# Escorna_CPU_2_10.net
KiCad netlist of a schematic drawn in EAGLE
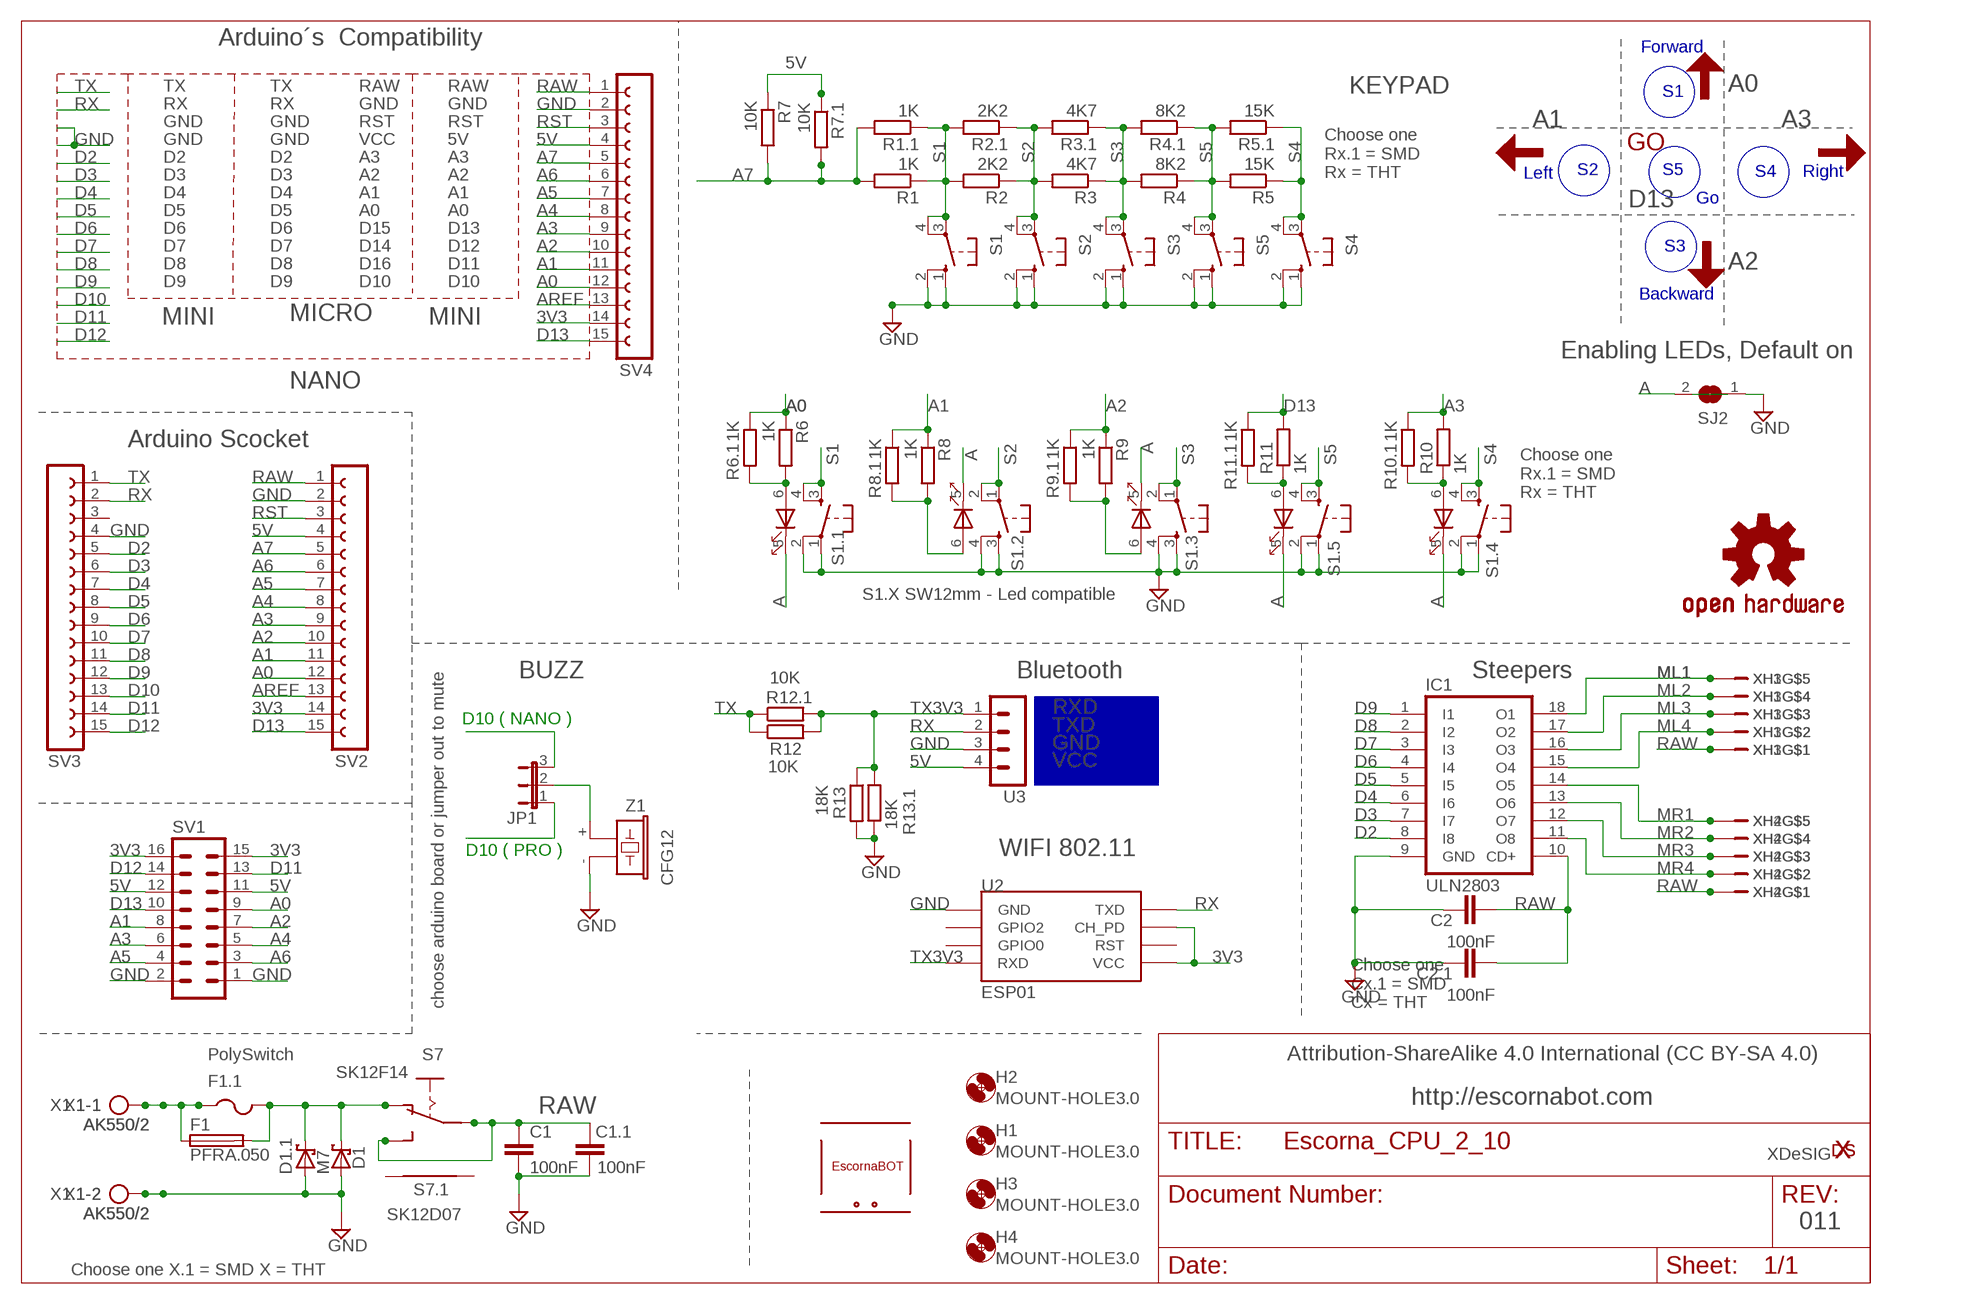
[diagram p0: schematic, sheet 1]

(export (version "E")
  (design (tool "Eeschema 10.0.6"))
  (components
    (comp (ref "C1")
      (value "100nF")
      (footprint "eagle-import:C025-025X050")
      (libsource (lib "eagle-import") (part "C-EU025-025X050"))
    )
    (comp (ref "C1.1")
      (value "100nF")
      (footprint "eagle-import:C1206")
      (libsource (lib "eagle-import") (part "C-EUC1206"))
    )
    (comp (ref "C2")
      (value "100nF")
      (footprint "eagle-import:C025-025X050")
      (libsource (lib "eagle-import") (part "C-EU025-025X050"))
    )
    (comp (ref "C2.1")
      (value "100nF")
      (footprint "eagle-import:C1206")
      (libsource (lib "eagle-import") (part "C-EUC1206"))
    )
    (comp (ref "D1")
      (value "1N5817")
      (footprint "eagle-import:DO41-10")
      (libsource (lib "eagle-import") (part "P4KEXX"))
    )
    (comp (ref "D1.1")
      (value "M7")
      (footprint "eagle-import:SMA")
      (libsource (lib "eagle-import") (part "SCHOTTKY-DIODESMA"))
    )
    (comp (ref "ESC")
      (value "ESCORNABOT")
      (footprint "eagle-import:ESCORNA_PEQUE")
      (libsource (lib "eagle-import") (part "ESCORNABOT"))
    )
    (comp (ref "F1")
      (value "PFRA.050")
      (footprint "eagle-import:TE5")
      (libsource (lib "eagle-import") (part "FUSETE5"))
    )
    (comp (ref "F1.1")
      (value "PolySwitch")
      (footprint "eagle-import:R1206")
      (libsource (lib "eagle-import") (part "PTCFUSE-1206"))
    )
    (comp (ref "H1")
      (value "MOUNT-HOLE3.0")
      (footprint "eagle-import:3,0")
      (libsource (lib "eagle-import") (part "MOUNT-HOLE3.0"))
    )
    (comp (ref "H2")
      (value "MOUNT-HOLE3.0")
      (footprint "eagle-import:3,0")
      (libsource (lib "eagle-import") (part "MOUNT-HOLE3.0"))
    )
    (comp (ref "H3")
      (value "MOUNT-HOLE3.0")
      (footprint "eagle-import:3,0")
      (libsource (lib "eagle-import") (part "MOUNT-HOLE3.0"))
    )
    (comp (ref "H4")
      (value "MOUNT-HOLE3.0")
      (footprint "eagle-import:3,0")
      (libsource (lib "eagle-import") (part "MOUNT-HOLE3.0"))
    )
    (comp (ref "IC1")
      (value "ULN2803")
      (footprint "eagle-import:DIL18")
      (libsource (lib "eagle-import") (part "ULN2803A"))
    )
    (comp (ref "JP1")
      (value "JUMPER_JP2E")
      (footprint "eagle-import:JUMPER_JP2")
      (libsource (lib "eagle-import") (part "JUMPER_JP2E"))
    )
    (comp (ref "LOGO2")
      (value "OSHW-LOGOS")
      (footprint "eagle-import:OSHW-LOGO-S")
      (libsource (lib "eagle-import") (part "OSHW-LOGOS"))
    )
    (comp (ref "R1")
      (value "1K")
      (footprint "eagle-import:0204_7")
      (libsource (lib "eagle-import") (part "R-EU_0204/7"))
    )
    (comp (ref "R1.1")
      (value "1K")
      (footprint "eagle-import:R0603")
      (libsource (lib "eagle-import") (part "R-EU_R0603"))
    )
    (comp (ref "R2")
      (value "2K2")
      (footprint "eagle-import:0204_7")
      (libsource (lib "eagle-import") (part "R-EU_0204/7"))
    )
    (comp (ref "R2.1")
      (value "2K2")
      (footprint "eagle-import:R0603")
      (libsource (lib "eagle-import") (part "R-EU_R0603"))
    )
    (comp (ref "R3")
      (value "4K7")
      (footprint "eagle-import:0204_7")
      (libsource (lib "eagle-import") (part "R-EU_0204/7"))
    )
    (comp (ref "R3.1")
      (value "4K7")
      (footprint "eagle-import:R0603")
      (libsource (lib "eagle-import") (part "R-EU_R0603"))
    )
    (comp (ref "R4")
      (value "8K2")
      (footprint "eagle-import:0204_7")
      (libsource (lib "eagle-import") (part "R-EU_0204/7"))
    )
    (comp (ref "R4.1")
      (value "8K2")
      (footprint "eagle-import:R0603")
      (libsource (lib "eagle-import") (part "R-EU_R0603"))
    )
    (comp (ref "R5")
      (value "15K")
      (footprint "eagle-import:0204_7")
      (libsource (lib "eagle-import") (part "R-EU_0204/7"))
    )
    (comp (ref "R5.1")
      (value "15K")
      (footprint "eagle-import:R0603")
      (libsource (lib "eagle-import") (part "R-EU_R0603"))
    )
    (comp (ref "R6")
      (value "1K")
      (footprint "eagle-import:0204_7")
      (libsource (lib "eagle-import") (part "R-EU_0204/7"))
    )
    (comp (ref "R6.1")
      (value "1K")
      (footprint "eagle-import:R0603")
      (libsource (lib "eagle-import") (part "R-EU_R0603"))
    )
    (comp (ref "R7")
      (value "10K")
      (footprint "eagle-import:0204_7")
      (libsource (lib "eagle-import") (part "R-EU_0204/7"))
    )
    (comp (ref "R7.1")
      (value "10K")
      (footprint "eagle-import:R0603")
      (libsource (lib "eagle-import") (part "R-EU_R0603"))
    )
    (comp (ref "R8")
      (value "1K")
      (footprint "eagle-import:0204_7")
      (libsource (lib "eagle-import") (part "R-EU_0204/7"))
    )
    (comp (ref "R8.1")
      (value "1K")
      (footprint "eagle-import:R0603")
      (libsource (lib "eagle-import") (part "R-EU_R0603"))
    )
    (comp (ref "R9")
      (value "1K")
      (footprint "eagle-import:0204_7")
      (libsource (lib "eagle-import") (part "R-EU_0204/7"))
    )
    (comp (ref "R9.1")
      (value "1K")
      (footprint "eagle-import:R0603")
      (libsource (lib "eagle-import") (part "R-EU_R0603"))
    )
    (comp (ref "R10")
      (value "1K")
      (footprint "eagle-import:0204_7")
      (libsource (lib "eagle-import") (part "R-EU_0204/7"))
    )
    (comp (ref "R10.1")
      (value "1K")
      (footprint "eagle-import:R0603")
      (libsource (lib "eagle-import") (part "R-EU_R0603"))
    )
    (comp (ref "R11")
      (value "1K")
      (footprint "eagle-import:0204_7")
      (libsource (lib "eagle-import") (part "R-EU_0204/7"))
    )
    (comp (ref "R11.1")
      (value "1K")
      (footprint "eagle-import:R0603")
      (libsource (lib "eagle-import") (part "R-EU_R0603"))
    )
    (comp (ref "R12")
      (value "10K")
      (footprint "eagle-import:0204_7")
      (libsource (lib "eagle-import") (part "R-EU_0204/7"))
    )
    (comp (ref "R12.1")
      (value "10K")
      (footprint "eagle-import:R0603")
      (libsource (lib "eagle-import") (part "R-EU_R0603"))
    )
    (comp (ref "R13")
      (value "18K")
      (footprint "eagle-import:0204_7")
      (libsource (lib "eagle-import") (part "R-EU_0204/7"))
    )
    (comp (ref "R13.1")
      (value "18K")
      (footprint "eagle-import:R0603")
      (libsource (lib "eagle-import") (part "R-EU_R0603"))
    )
    (comp (ref "S1")
      (value "10-XX")
      (footprint "eagle-import:B3F-10XX")
      (fields (field (name "MPN") "B3F-1000"))
      (libsource (lib "eagle-import") (part "10-XX"))
    )
    (comp (ref "S1.1")
      (value "B3F-9XXX")
      (footprint "eagle-import:B3F-9XXX")
      (libsource (lib "eagle-import") (part "SWITCH-OMRON_B3F-9XXX"))
    )
    (comp (ref "S1.2")
      (value "B3F-9XXX")
      (footprint "eagle-import:B3F-9XXX")
      (libsource (lib "eagle-import") (part "SWITCH-OMRON_B3F-9XXX"))
    )
    (comp (ref "S1.3")
      (value "B3F-9XXX")
      (footprint "eagle-import:B3F-9XXX")
      (libsource (lib "eagle-import") (part "SWITCH-OMRON_B3F-9XXX"))
    )
    (comp (ref "S1.4")
      (value "B3F-9XXX")
      (footprint "eagle-import:B3F-9XXX")
      (libsource (lib "eagle-import") (part "SWITCH-OMRON_B3F-9XXX"))
    )
    (comp (ref "S1.5")
      (value "B3F-9XXX")
      (footprint "eagle-import:B3F-9XXX")
      (libsource (lib "eagle-import") (part "SWITCH-OMRON_B3F-9XXX"))
    )
    (comp (ref "S2")
      (value "10-XX")
      (footprint "eagle-import:B3F-10XX")
      (fields (field (name "MPN") "B3F-1000"))
      (libsource (lib "eagle-import") (part "10-XX"))
    )
    (comp (ref "S3")
      (value "10-XX")
      (footprint "eagle-import:B3F-10XX")
      (fields (field (name "MPN") "B3F-1000"))
      (libsource (lib "eagle-import") (part "10-XX"))
    )
    (comp (ref "S4")
      (value "10-XX")
      (footprint "eagle-import:B3F-10XX")
      (fields (field (name "MPN") "B3F-1000"))
      (libsource (lib "eagle-import") (part "10-XX"))
    )
    (comp (ref "S5")
      (value "10-XX")
      (footprint "eagle-import:B3F-10XX")
      (fields (field (name "MPN") "B3F-1000"))
      (libsource (lib "eagle-import") (part "10-XX"))
    )
    (comp (ref "S7")
      (value "SK12F14")
      (footprint "eagle-import:ESCORNA_SK-12F14-G")
      (libsource (lib "eagle-import") (part "ESCORNA_SK12F14F"))
    )
    (comp (ref "S7.1")
      (value "SK12D07")
      (footprint "eagle-import:ESCORNA_SK-12D07")
      (libsource (lib "eagle-import") (part "ESCORNA_SK12F14D"))
    )
    (comp (ref "SJ2") (value "SJ") (footprint "eagle-import:SJ") (libsource (lib "eagle-import") (part "SJ")))
    (comp (ref "SV1")
      (value "MA08-2")
      (footprint "eagle-import:MA08-2")
      (libsource (lib "eagle-import") (part "MA08-2"))
    )
    (comp (ref "SV2")
      (value "CON-LSTA_FE15-1")
      (footprint "eagle-import:CON-LSTA_FE15")
      (libsource (lib "eagle-import") (part "CON-LSTA_FE15-1"))
    )
    (comp (ref "SV3")
      (value "CON-LSTA_FE15-1")
      (footprint "eagle-import:CON-LSTA_FE15")
      (libsource (lib "eagle-import") (part "CON-LSTA_FE15-1"))
    )
    (comp (ref "SV4")
      (value "CON-LSTA_FE15-1")
      (footprint "eagle-import:CON-LSTA_FE15")
      (fields (field (name "OC_FARNELL") "unknown") (field (name "OC_NEWARK") "unknown"))
      (libsource (lib "eagle-import") (part "CON-LSTA_FE15-1"))
    )
    (comp (ref "U$1")
      (value "FRECHA")
      (footprint "eagle-import:FRECHA")
      (libsource (lib "eagle-import") (part "FRECHA"))
    )
    (comp (ref "U$2")
      (value "GO")
      (footprint "eagle-import:VALE")
      (libsource (lib "eagle-import") (part "GO"))
    )
    (comp (ref "U$3")
      (value "FRECHA")
      (footprint "eagle-import:FRECHA")
      (libsource (lib "eagle-import") (part "FRECHA"))
    )
    (comp (ref "U$6")
      (value "FRECHA")
      (footprint "eagle-import:FRECHA")
      (libsource (lib "eagle-import") (part "FRECHA"))
    )
    (comp (ref "U$11")
      (value "FRECHA")
      (footprint "eagle-import:FRECHA")
      (libsource (lib "eagle-import") (part "FRECHA"))
    )
    (comp (ref "U$13")
      (value "XDESIG_XDESIG21")
      (footprint "eagle-import:XDESIG_XDESIG")
      (libsource (lib "eagle-import") (part "XDESIG_XDESIG21"))
    )
    (comp (ref "U2")
      (value "ESP01")
      (footprint "eagle-import:ESP01")
      (libsource (lib "eagle-import") (part "ESP01"))
    )
    (comp (ref "U3")
      (value "MA04-1")
      (footprint "eagle-import:MA04-1")
      (libsource (lib "eagle-import") (part "MA04-1"))
    )
    (comp (ref "X1")
      (value "AK550/2")
      (footprint "eagle-import:AK550_2")
      (libsource (lib "eagle-import") (part "AK550/2"))
    )
    (comp (ref "X1.1")
      (value "AK550/2")
      (footprint "eagle-import:AK550_2")
      (fields (field (name "OC_FARNELL") "unknown") (field (name "OC_NEWARK") "unknown"))
      (libsource (lib "eagle-import") (part "AK550/2"))
    )
    (comp (ref "XDS1")
      (value "XDESIG")
      (footprint "eagle-import:XDESIG_CU_2")
      (libsource (lib "eagle-import") (part "XDESIG"))
    )
    (comp (ref "XH1")
      (value "B5B-XH-A")
      (footprint "eagle-import:B5B-XH-A")
      (libsource (lib "eagle-import") (part "B5B-XH-A"))
    )
    (comp (ref "XH2")
      (value "B5B-XH-A")
      (footprint "eagle-import:B5B-XH-A")
      (libsource (lib "eagle-import") (part "B5B-XH-A"))
    )
    (comp (ref "XH3")
      (value "B5B-XH-A")
      (footprint "eagle-import:B5B-XH-A")
      (libsource (lib "eagle-import") (part "B5B-XH-A"))
    )
    (comp (ref "XH4")
      (value "B5B-XH-A")
      (footprint "eagle-import:B5B-XH-A")
      (libsource (lib "eagle-import") (part "B5B-XH-A"))
    )
    (comp (ref "Z1")
      (value "CFG12")
      (footprint "eagle-import:F_CM12P")
      (libsource (lib "eagle-import") (part "F/CM12P"))
    )
  )
  (nets
    (net (code "1") (name "/3V3") (class "Default")
      (node (ref "SV1") (pin "15") (pinfunction "15_15") (pintype "passive"))
      (node (ref "SV1") (pin "16") (pinfunction "16_16") (pintype "passive"))
      (node (ref "SV2") (pin "14") (pinfunction "14_14") (pintype "passive"))
      (node (ref "SV4") (pin "14") (pinfunction "14_14") (pintype "passive"))
      (node (ref "U2") (pin "CH_PD") (pinfunction "CH_PD_CH_PD") (pintype "bidirectional"))
      (node (ref "U2") (pin "VCC") (pinfunction "VCC_VCC") (pintype "bidirectional"))
    )
    (net (code "2") (name "/5V") (class "Default")
      (node (ref "R7") (pin "1") (pinfunction "1_1") (pintype "passive"))
      (node (ref "R7.1") (pin "1") (pinfunction "1_1") (pintype "passive"))
      (node (ref "SV1") (pin "11") (pinfunction "11_11") (pintype "passive"))
      (node (ref "SV1") (pin "12") (pinfunction "12_12") (pintype "passive"))
      (node (ref "SV2") (pin "4") (pinfunction "4_4") (pintype "passive"))
      (node (ref "SV4") (pin "4") (pinfunction "4_4") (pintype "passive"))
      (node (ref "U3") (pin "4") (pinfunction "4_4") (pintype "passive"))
    )
    (net (code "3") (name "/A") (class "Default")
      (node (ref "S1.1") (pin "5") (pinfunction "K_5") (pintype "passive"))
      (node (ref "S1.2") (pin "5") (pinfunction "K_5") (pintype "passive"))
      (node (ref "S1.3") (pin "5") (pinfunction "K_5") (pintype "passive"))
      (node (ref "S1.4") (pin "5") (pinfunction "K_5") (pintype "passive"))
      (node (ref "S1.5") (pin "5") (pinfunction "K_5") (pintype "passive"))
      (node (ref "SJ2") (pin "2") (pinfunction "2_2") (pintype "passive"))
    )
    (net (code "4") (name "/A0") (class "Default")
      (node (ref "JP1") (pin "1") (pinfunction "1_1") (pintype "passive"))
      (node (ref "R6") (pin "1") (pinfunction "1_1") (pintype "passive"))
      (node (ref "R6.1") (pin "1") (pinfunction "1_1") (pintype "passive"))
      (node (ref "SV1") (pin "9") (pinfunction "9_9") (pintype "passive"))
      (node (ref "SV2") (pin "12") (pinfunction "12_12") (pintype "passive"))
      (node (ref "SV4") (pin "12") (pinfunction "12_12") (pintype "passive"))
    )
    (net (code "5") (name "/A1") (class "Default")
      (node (ref "R8") (pin "1") (pinfunction "1_1") (pintype "passive"))
      (node (ref "R8.1") (pin "1") (pinfunction "1_1") (pintype "passive"))
      (node (ref "SV1") (pin "8") (pinfunction "8_8") (pintype "passive"))
      (node (ref "SV2") (pin "11") (pinfunction "11_11") (pintype "passive"))
      (node (ref "SV4") (pin "11") (pinfunction "11_11") (pintype "passive"))
    )
    (net (code "6") (name "/A2") (class "Default")
      (node (ref "R9") (pin "1") (pinfunction "1_1") (pintype "passive"))
      (node (ref "R9.1") (pin "1") (pinfunction "1_1") (pintype "passive"))
      (node (ref "SV1") (pin "7") (pinfunction "7_7") (pintype "passive"))
      (node (ref "SV2") (pin "10") (pinfunction "10_10") (pintype "passive"))
      (node (ref "SV4") (pin "10") (pinfunction "10_10") (pintype "passive"))
    )
    (net (code "7") (name "/A3") (class "Default")
      (node (ref "R10") (pin "2") (pinfunction "2_2") (pintype "passive"))
      (node (ref "R10.1") (pin "1") (pinfunction "1_1") (pintype "passive"))
      (node (ref "SV1") (pin "6") (pinfunction "6_6") (pintype "passive"))
      (node (ref "SV2") (pin "9") (pinfunction "9_9") (pintype "passive"))
      (node (ref "SV4") (pin "9") (pinfunction "9_9") (pintype "passive"))
    )
    (net (code "8") (name "/A4") (class "Default")
      (node (ref "SV1") (pin "5") (pinfunction "5_5") (pintype "passive"))
      (node (ref "SV2") (pin "8") (pinfunction "8_8") (pintype "passive"))
      (node (ref "SV4") (pin "8") (pinfunction "8_8") (pintype "passive"))
    )
    (net (code "9") (name "/A5") (class "Default")
      (node (ref "SV1") (pin "4") (pinfunction "4_4") (pintype "passive"))
      (node (ref "SV2") (pin "7") (pinfunction "7_7") (pintype "passive"))
      (node (ref "SV4") (pin "7") (pinfunction "7_7") (pintype "passive"))
    )
    (net (code "10") (name "/A6") (class "Default")
      (node (ref "SV1") (pin "3") (pinfunction "3_3") (pintype "passive"))
      (node (ref "SV2") (pin "6") (pinfunction "6_6") (pintype "passive"))
      (node (ref "SV4") (pin "6") (pinfunction "6_6") (pintype "passive"))
    )
    (net (code "11") (name "/A7") (class "Default")
      (node (ref "R1") (pin "2") (pinfunction "2_2") (pintype "passive"))
      (node (ref "R1.1") (pin "2") (pinfunction "2_2") (pintype "passive"))
      (node (ref "R7") (pin "2") (pinfunction "2_2") (pintype "passive"))
      (node (ref "R7.1") (pin "2") (pinfunction "2_2") (pintype "passive"))
      (node (ref "SV2") (pin "5") (pinfunction "5_5") (pintype "passive"))
      (node (ref "SV4") (pin "5") (pinfunction "5_5") (pintype "passive"))
    )
    (net (code "12") (name "/AREF") (class "Default")
      (node (ref "SV2") (pin "13") (pinfunction "13_13") (pintype "passive"))
      (node (ref "SV4") (pin "13") (pinfunction "13_13") (pintype "passive"))
    )
    (net (code "13") (name "/D2") (class "Default")
      (node (ref "IC1") (pin "8") (pinfunction "I8_8") (pintype "input"))
      (node (ref "SV3") (pin "5") (pinfunction "5_5") (pintype "passive"))
    )
    (net (code "14") (name "/D3") (class "Default")
      (node (ref "IC1") (pin "7") (pinfunction "I7_7") (pintype "input"))
      (node (ref "SV3") (pin "6") (pinfunction "6_6") (pintype "passive"))
    )
    (net (code "15") (name "/D4") (class "Default")
      (node (ref "IC1") (pin "6") (pinfunction "I6_6") (pintype "input"))
      (node (ref "SV3") (pin "7") (pinfunction "7_7") (pintype "passive"))
    )
    (net (code "16") (name "/D5") (class "Default")
      (node (ref "IC1") (pin "5") (pinfunction "I5_5") (pintype "input"))
      (node (ref "SV3") (pin "8") (pinfunction "8_8") (pintype "passive"))
    )
    (net (code "17") (name "/D6") (class "Default")
      (node (ref "IC1") (pin "4") (pinfunction "I4_4") (pintype "input"))
      (node (ref "SV3") (pin "9") (pinfunction "9_9") (pintype "passive"))
    )
    (net (code "18") (name "/D7") (class "Default")
      (node (ref "IC1") (pin "3") (pinfunction "I3_3") (pintype "input"))
      (node (ref "SV3") (pin "10") (pinfunction "10_10") (pintype "passive"))
    )
    (net (code "19") (name "/D8") (class "Default")
      (node (ref "IC1") (pin "2") (pinfunction "I2_2") (pintype "input"))
      (node (ref "SV3") (pin "11") (pinfunction "11_11") (pintype "passive"))
    )
    (net (code "20") (name "/D9") (class "Default")
      (node (ref "IC1") (pin "1") (pinfunction "I1_1") (pintype "input"))
      (node (ref "SV3") (pin "12") (pinfunction "12_12") (pintype "passive"))
    )
    (net (code "21") (name "/D10") (class "Default")
      (node (ref "JP1") (pin "3") (pinfunction "3_3") (pintype "passive"))
      (node (ref "SV3") (pin "13") (pinfunction "13_13") (pintype "passive"))
    )
    (net (code "22") (name "/D11") (class "Default")
      (node (ref "SV1") (pin "13") (pinfunction "13_13") (pintype "passive"))
      (node (ref "SV3") (pin "14") (pinfunction "14_14") (pintype "passive"))
    )
    (net (code "23") (name "/D12") (class "Default")
      (node (ref "SV1") (pin "14") (pinfunction "14_14") (pintype "passive"))
      (node (ref "SV3") (pin "15") (pinfunction "15_15") (pintype "passive"))
    )
    (net (code "24") (name "/D13") (class "Default")
      (node (ref "R11") (pin "2") (pinfunction "2_2") (pintype "passive"))
      (node (ref "R11.1") (pin "1") (pinfunction "1_1") (pintype "passive"))
      (node (ref "SV1") (pin "10") (pinfunction "10_10") (pintype "passive"))
      (node (ref "SV2") (pin "15") (pinfunction "15_15") (pintype "passive"))
      (node (ref "SV4") (pin "15") (pinfunction "15_15") (pintype "passive"))
    )
    (net (code "25") (name "/ML1") (class "Default")
      (node (ref "IC1") (pin "18") (pinfunction "O1_18") (pintype "open_collector"))
      (node (ref "XH1") (pin "P$5") (pinfunction "1_P$5") (pintype "passive"))
      (node (ref "XH3") (pin "P$5") (pinfunction "1_P$5") (pintype "passive"))
    )
    (net (code "26") (name "/ML2") (class "Default")
      (node (ref "IC1") (pin "17") (pinfunction "O2_17") (pintype "open_collector"))
      (node (ref "XH1") (pin "P$4") (pinfunction "1_P$4") (pintype "passive"))
      (node (ref "XH3") (pin "P$4") (pinfunction "1_P$4") (pintype "passive"))
    )
    (net (code "27") (name "/ML3") (class "Default")
      (node (ref "IC1") (pin "16") (pinfunction "O3_16") (pintype "open_collector"))
      (node (ref "XH1") (pin "P$3") (pinfunction "1_P$3") (pintype "passive"))
      (node (ref "XH3") (pin "P$3") (pinfunction "1_P$3") (pintype "passive"))
    )
    (net (code "28") (name "/ML4") (class "Default")
      (node (ref "IC1") (pin "15") (pinfunction "O4_15") (pintype "open_collector"))
      (node (ref "XH1") (pin "P$2") (pinfunction "1_P$2") (pintype "passive"))
      (node (ref "XH3") (pin "P$2") (pinfunction "1_P$2") (pintype "passive"))
    )
    (net (code "29") (name "/MR1") (class "Default")
      (node (ref "IC1") (pin "14") (pinfunction "O5_14") (pintype "open_collector"))
      (node (ref "XH2") (pin "P$5") (pinfunction "1_P$5") (pintype "passive"))
      (node (ref "XH4") (pin "P$5") (pinfunction "1_P$5") (pintype "passive"))
    )
    (net (code "30") (name "/MR2") (class "Default")
      (node (ref "IC1") (pin "13") (pinfunction "O6_13") (pintype "open_collector"))
      (node (ref "XH2") (pin "P$4") (pinfunction "1_P$4") (pintype "passive"))
      (node (ref "XH4") (pin "P$4") (pinfunction "1_P$4") (pintype "passive"))
    )
    (net (code "31") (name "/MR3") (class "Default")
      (node (ref "IC1") (pin "12") (pinfunction "O7_12") (pintype "open_collector"))
      (node (ref "XH2") (pin "P$3") (pinfunction "1_P$3") (pintype "passive"))
      (node (ref "XH4") (pin "P$3") (pinfunction "1_P$3") (pintype "passive"))
    )
    (net (code "32") (name "/MR4") (class "Default")
      (node (ref "IC1") (pin "11") (pinfunction "O8_11") (pintype "open_collector"))
      (node (ref "XH2") (pin "P$2") (pinfunction "1_P$2") (pintype "passive"))
      (node (ref "XH4") (pin "P$2") (pinfunction "1_P$2") (pintype "passive"))
    )
    (net (code "33") (name "/RAW") (class "Default")
      (node (ref "C1") (pin "1") (pinfunction "1_1") (pintype "passive"))
      (node (ref "C1.1") (pin "2") (pinfunction "2_2") (pintype "passive"))
      (node (ref "C2") (pin "2") (pinfunction "2_2") (pintype "passive"))
      (node (ref "C2.1") (pin "2") (pinfunction "2_2") (pintype "passive"))
      (node (ref "IC1") (pin "10") (pinfunction "CD+_10") (pintype "passive"))
      (node (ref "S7") (pin "P$1") (pinfunction "P_P$1") (pintype "passive"))
      (node (ref "S7") (pin "P$3") (pinfunction "S_P$3") (pintype "passive"))
      (node (ref "S7.1") (pin "P$1") (pinfunction "P_P$1") (pintype "passive"))
      (node (ref "S7.1") (pin "P$3") (pinfunction "S_P$3") (pintype "passive"))
      (node (ref "SV2") (pin "1") (pinfunction "1_1") (pintype "passive"))
      (node (ref "SV4") (pin "1") (pinfunction "1_1") (pintype "passive"))
      (node (ref "XH1") (pin "P$1") (pinfunction "1_P$1") (pintype "passive"))
      (node (ref "XH2") (pin "P$1") (pinfunction "1_P$1") (pintype "passive"))
      (node (ref "XH3") (pin "P$1") (pinfunction "1_P$1") (pintype "passive"))
      (node (ref "XH4") (pin "P$1") (pinfunction "1_P$1") (pintype "passive"))
    )
    (net (code "34") (name "/RST") (class "Default")
      (node (ref "SV2") (pin "3") (pinfunction "3_3") (pintype "passive"))
      (node (ref "SV4") (pin "3") (pinfunction "3_3") (pintype "passive"))
    )
    (net (code "35") (name "/RX") (class "Default")
      (node (ref "SV3") (pin "2") (pinfunction "2_2") (pintype "passive"))
      (node (ref "U2") (pin "TX") (pinfunction "TXD_TX") (pintype "bidirectional"))
      (node (ref "U3") (pin "2") (pinfunction "2_2") (pintype "passive"))
    )
    (net (code "36") (name "/S1") (class "Default")
      (node (ref "R1") (pin "1") (pinfunction "1_1") (pintype "passive"))
      (node (ref "R1.1") (pin "1") (pinfunction "1_1") (pintype "passive"))
      (node (ref "R2") (pin "2") (pinfunction "2_2") (pintype "passive"))
      (node (ref "R2.1") (pin "2") (pinfunction "2_2") (pintype "passive"))
      (node (ref "S1") (pin "3") (pinfunction "P_3") (pintype "passive"))
      (node (ref "S1") (pin "4") (pinfunction "P1_4") (pintype "passive"))
      (node (ref "S1.1") (pin "3") (pinfunction "S_3") (pintype "passive"))
      (node (ref "S1.1") (pin "4") (pinfunction "S1_4") (pintype "passive"))
    )
    (net (code "37") (name "/S2") (class "Default")
      (node (ref "R2") (pin "1") (pinfunction "1_1") (pintype "passive"))
      (node (ref "R2.1") (pin "1") (pinfunction "1_1") (pintype "passive"))
      (node (ref "R3") (pin "2") (pinfunction "2_2") (pintype "passive"))
      (node (ref "R3.1") (pin "2") (pinfunction "2_2") (pintype "passive"))
      (node (ref "S1.2") (pin "1") (pinfunction "P_1") (pintype "passive"))
      (node (ref "S1.2") (pin "2") (pinfunction "P1_2") (pintype "passive"))
      (node (ref "S2") (pin "3") (pinfunction "P_3") (pintype "passive"))
      (node (ref "S2") (pin "4") (pinfunction "P1_4") (pintype "passive"))
    )
    (net (code "38") (name "/S3") (class "Default")
      (node (ref "R3") (pin "1") (pinfunction "1_1") (pintype "passive"))
      (node (ref "R3.1") (pin "1") (pinfunction "1_1") (pintype "passive"))
      (node (ref "R4") (pin "2") (pinfunction "2_2") (pintype "passive"))
      (node (ref "R4.1") (pin "2") (pinfunction "2_2") (pintype "passive"))
      (node (ref "S1.3") (pin "1") (pinfunction "P_1") (pintype "passive"))
      (node (ref "S1.3") (pin "2") (pinfunction "P1_2") (pintype "passive"))
      (node (ref "S3") (pin "3") (pinfunction "P_3") (pintype "passive"))
      (node (ref "S3") (pin "4") (pinfunction "P1_4") (pintype "passive"))
    )
    (net (code "39") (name "/S4") (class "Default")
      (node (ref "R5") (pin "1") (pinfunction "1_1") (pintype "passive"))
      (node (ref "R5.1") (pin "1") (pinfunction "1_1") (pintype "passive"))
      (node (ref "S1.4") (pin "3") (pinfunction "S_3") (pintype "passive"))
      (node (ref "S1.4") (pin "4") (pinfunction "S1_4") (pintype "passive"))
      (node (ref "S4") (pin "3") (pinfunction "P_3") (pintype "passive"))
      (node (ref "S4") (pin "4") (pinfunction "P1_4") (pintype "passive"))
    )
    (net (code "40") (name "/S5") (class "Default")
      (node (ref "R4") (pin "1") (pinfunction "1_1") (pintype "passive"))
      (node (ref "R4.1") (pin "1") (pinfunction "1_1") (pintype "passive"))
      (node (ref "R5") (pin "2") (pinfunction "2_2") (pintype "passive"))
      (node (ref "R5.1") (pin "2") (pinfunction "2_2") (pintype "passive"))
      (node (ref "S1.5") (pin "3") (pinfunction "S_3") (pintype "passive"))
      (node (ref "S1.5") (pin "4") (pinfunction "S1_4") (pintype "passive"))
      (node (ref "S5") (pin "3") (pinfunction "P_3") (pintype "passive"))
      (node (ref "S5") (pin "4") (pinfunction "P1_4") (pintype "passive"))
    )
    (net (code "41") (name "/TX") (class "Default")
      (node (ref "R12") (pin "1") (pinfunction "1_1") (pintype "passive"))
      (node (ref "R12.1") (pin "1") (pinfunction "1_1") (pintype "passive"))
      (node (ref "SV3") (pin "1") (pinfunction "1_1") (pintype "passive"))
    )
    (net (code "42") (name "/TX3V3") (class "Default")
      (node (ref "R12") (pin "2") (pinfunction "2_2") (pintype "passive"))
      (node (ref "R12.1") (pin "2") (pinfunction "2_2") (pintype "passive"))
      (node (ref "R13") (pin "1") (pinfunction "1_1") (pintype "passive"))
      (node (ref "R13.1") (pin "2") (pinfunction "2_2") (pintype "passive"))
      (node (ref "U2") (pin "RX") (pinfunction "RXD_RX") (pintype "bidirectional"))
      (node (ref "U3") (pin "1") (pinfunction "1_1") (pintype "passive"))
    )
    (net (code "43") (name "GND") (class "Default")
      (node (ref "C1") (pin "2") (pinfunction "2_2") (pintype "passive"))
      (node (ref "C1.1") (pin "1") (pinfunction "1_1") (pintype "passive"))
      (node (ref "C2") (pin "1") (pinfunction "1_1") (pintype "passive"))
      (node (ref "C2.1") (pin "1") (pinfunction "1_1") (pintype "passive"))
      (node (ref "D1") (pin "A") (pinfunction "A_A") (pintype "passive"))
      (node (ref "D1.1") (pin "A") (pinfunction "A_A") (pintype "passive"))
      (node (ref "IC1") (pin "9") (pinfunction "GND_9") (pintype "power_in"))
      (node (ref "R13") (pin "2") (pinfunction "2_2") (pintype "passive"))
      (node (ref "R13.1") (pin "1") (pinfunction "1_1") (pintype "passive"))
      (node (ref "S1") (pin "1") (pinfunction "S_1") (pintype "passive"))
      (node (ref "S1") (pin "2") (pinfunction "S1_2") (pintype "passive"))
      (node (ref "S1.1") (pin "1") (pinfunction "P_1") (pintype "passive"))
      (node (ref "S1.1") (pin "2") (pinfunction "P1_2") (pintype "passive"))
      (node (ref "S1.2") (pin "3") (pinfunction "S_3") (pintype "passive"))
      (node (ref "S1.2") (pin "4") (pinfunction "S1_4") (pintype "passive"))
      (node (ref "S1.3") (pin "3") (pinfunction "S_3") (pintype "passive"))
      (node (ref "S1.3") (pin "4") (pinfunction "S1_4") (pintype "passive"))
      (node (ref "S1.4") (pin "1") (pinfunction "P_1") (pintype "passive"))
      (node (ref "S1.4") (pin "2") (pinfunction "P1_2") (pintype "passive"))
      (node (ref "S1.5") (pin "1") (pinfunction "P_1") (pintype "passive"))
      (node (ref "S1.5") (pin "2") (pinfunction "P1_2") (pintype "passive"))
      (node (ref "S2") (pin "1") (pinfunction "S_1") (pintype "passive"))
      (node (ref "S2") (pin "2") (pinfunction "S1_2") (pintype "passive"))
      (node (ref "S3") (pin "1") (pinfunction "S_1") (pintype "passive"))
      (node (ref "S3") (pin "2") (pinfunction "S1_2") (pintype "passive"))
      (node (ref "S4") (pin "1") (pinfunction "S_1") (pintype "passive"))
      (node (ref "S4") (pin "2") (pinfunction "S1_2") (pintype "passive"))
      (node (ref "S5") (pin "1") (pinfunction "S_1") (pintype "passive"))
      (node (ref "S5") (pin "2") (pinfunction "S1_2") (pintype "passive"))
      (node (ref "SJ2") (pin "1") (pinfunction "1_1") (pintype "passive"))
      (node (ref "SV1") (pin "1") (pinfunction "1_1") (pintype "passive"))
      (node (ref "SV1") (pin "2") (pinfunction "2_2") (pintype "passive"))
      (node (ref "SV2") (pin "2") (pinfunction "2_2") (pintype "passive"))
      (node (ref "SV3") (pin "4") (pinfunction "4_4") (pintype "passive"))
      (node (ref "SV4") (pin "2") (pinfunction "2_2") (pintype "passive"))
      (node (ref "U2") (pin "GND") (pinfunction "GND_GND") (pintype "bidirectional"))
      (node (ref "U3") (pin "3") (pinfunction "3_3") (pintype "passive"))
      (node (ref "X1") (pin "2") (pinfunction "KL_2") (pintype "passive"))
      (node (ref "X1.1") (pin "2") (pinfunction "KL_2") (pintype "passive"))
      (node (ref "Z1") (pin "-") (pinfunction "2_-") (pintype "passive"))
    )
    (net (code "44") (name "Net-(S1.1-A)") (class "Default")
      (node (ref "R6") (pin "2") (pinfunction "2_2") (pintype "passive"))
      (node (ref "R6.1") (pin "2") (pinfunction "2_2") (pintype "passive"))
      (node (ref "S1.1") (pin "6") (pinfunction "A_6") (pintype "passive"))
    )
    (net (code "45") (name "Net-(S1.2-A)") (class "Default")
      (node (ref "R8") (pin "2") (pinfunction "2_2") (pintype "passive"))
      (node (ref "R8.1") (pin "2") (pinfunction "2_2") (pintype "passive"))
      (node (ref "S1.2") (pin "6") (pinfunction "A_6") (pintype "passive"))
    )
    (net (code "46") (name "Net-(S1.3-A)") (class "Default")
      (node (ref "R9") (pin "2") (pinfunction "2_2") (pintype "passive"))
      (node (ref "R9.1") (pin "2") (pinfunction "2_2") (pintype "passive"))
      (node (ref "S1.3") (pin "6") (pinfunction "A_6") (pintype "passive"))
    )
    (net (code "47") (name "Net-(S1.4-A)") (class "Default")
      (node (ref "R10") (pin "1") (pinfunction "1_1") (pintype "passive"))
      (node (ref "R10.1") (pin "2") (pinfunction "2_2") (pintype "passive"))
      (node (ref "S1.4") (pin "6") (pinfunction "A_6") (pintype "passive"))
    )
    (net (code "48") (name "Net-(S1.5-A)") (class "Default")
      (node (ref "R11") (pin "1") (pinfunction "1_1") (pintype "passive"))
      (node (ref "R11.1") (pin "2") (pinfunction "2_2") (pintype "passive"))
      (node (ref "S1.5") (pin "6") (pinfunction "A_6") (pintype "passive"))
    )
    (net (code "49") (name "Net-(S7-O)") (class "Default")
      (node (ref "D1") (pin "C") (pinfunction "C_C") (pintype "passive"))
      (node (ref "D1.1") (pin "C") (pinfunction "C_C") (pintype "passive"))
      (node (ref "F1") (pin "2") (pinfunction "2_2") (pintype "passive"))
      (node (ref "F1.1") (pin "2") (pinfunction "2_2") (pintype "passive"))
      (node (ref "S7") (pin "P$2") (pinfunction "O_P$2") (pintype "passive"))
      (node (ref "S7.1") (pin "P$2") (pinfunction "O_P$2") (pintype "passive"))
    )
    (net (code "50") (name "Net-(S7-P$1)") (class "Default")
      (node (ref "S7") (pin "P$4") (pinfunction "P$1_P$4") (pintype "passive"))
      (node (ref "S7.1") (pin "P$4") (pinfunction "P$1_P$4") (pintype "passive"))
    )
    (net (code "51") (name "Net-(S7-P$2)") (class "Default")
      (node (ref "S7") (pin "P$5") (pinfunction "P$2_P$5") (pintype "bidirectional"))
      (node (ref "S7.1") (pin "P$5") (pinfunction "P$2_P$5") (pintype "bidirectional"))
    )
    (net (code "52") (name "Net-(X1.1A-KL)") (class "Default")
      (node (ref "F1") (pin "1") (pinfunction "1_1") (pintype "passive"))
      (node (ref "F1.1") (pin "1") (pinfunction "1_1") (pintype "passive"))
      (node (ref "X1") (pin "1") (pinfunction "KL_1") (pintype "passive"))
      (node (ref "X1.1") (pin "1") (pinfunction "KL_1") (pintype "passive"))
    )
    (net (code "53") (name "Net-(Z1-1)") (class "Default")
      (node (ref "JP1") (pin "2") (pinfunction "2_2") (pintype "passive"))
      (node (ref "Z1") (pin "+") (pinfunction "1_+") (pintype "passive"))
    )
    (net (code "54") (name "unconnected-(SV3-Pad3)") (class "Default")
      (node (ref "SV3") (pin "3") (pinfunction "3_3") (pintype "passive"))
    )
    (net (code "55") (name "unconnected-(U2-PadGPIO0)") (class "Default")
      (node (ref "U2") (pin "GPIO0") (pinfunction "GPIO0_GPIO0") (pintype "bidirectional"))
    )
    (net (code "56") (name "unconnected-(U2-PadGPIO2)") (class "Default")
      (node (ref "U2") (pin "GPIO2") (pinfunction "GPIO2_GPIO2") (pintype "bidirectional"))
    )
    (net (code "57") (name "unconnected-(U2-PadRST)") (class "Default")
      (node (ref "U2") (pin "RST") (pinfunction "RST_RST") (pintype "bidirectional"))
    )
  )
)
